# Schematics.net
KiCad netlist of a schematic drawn in Altium Designer
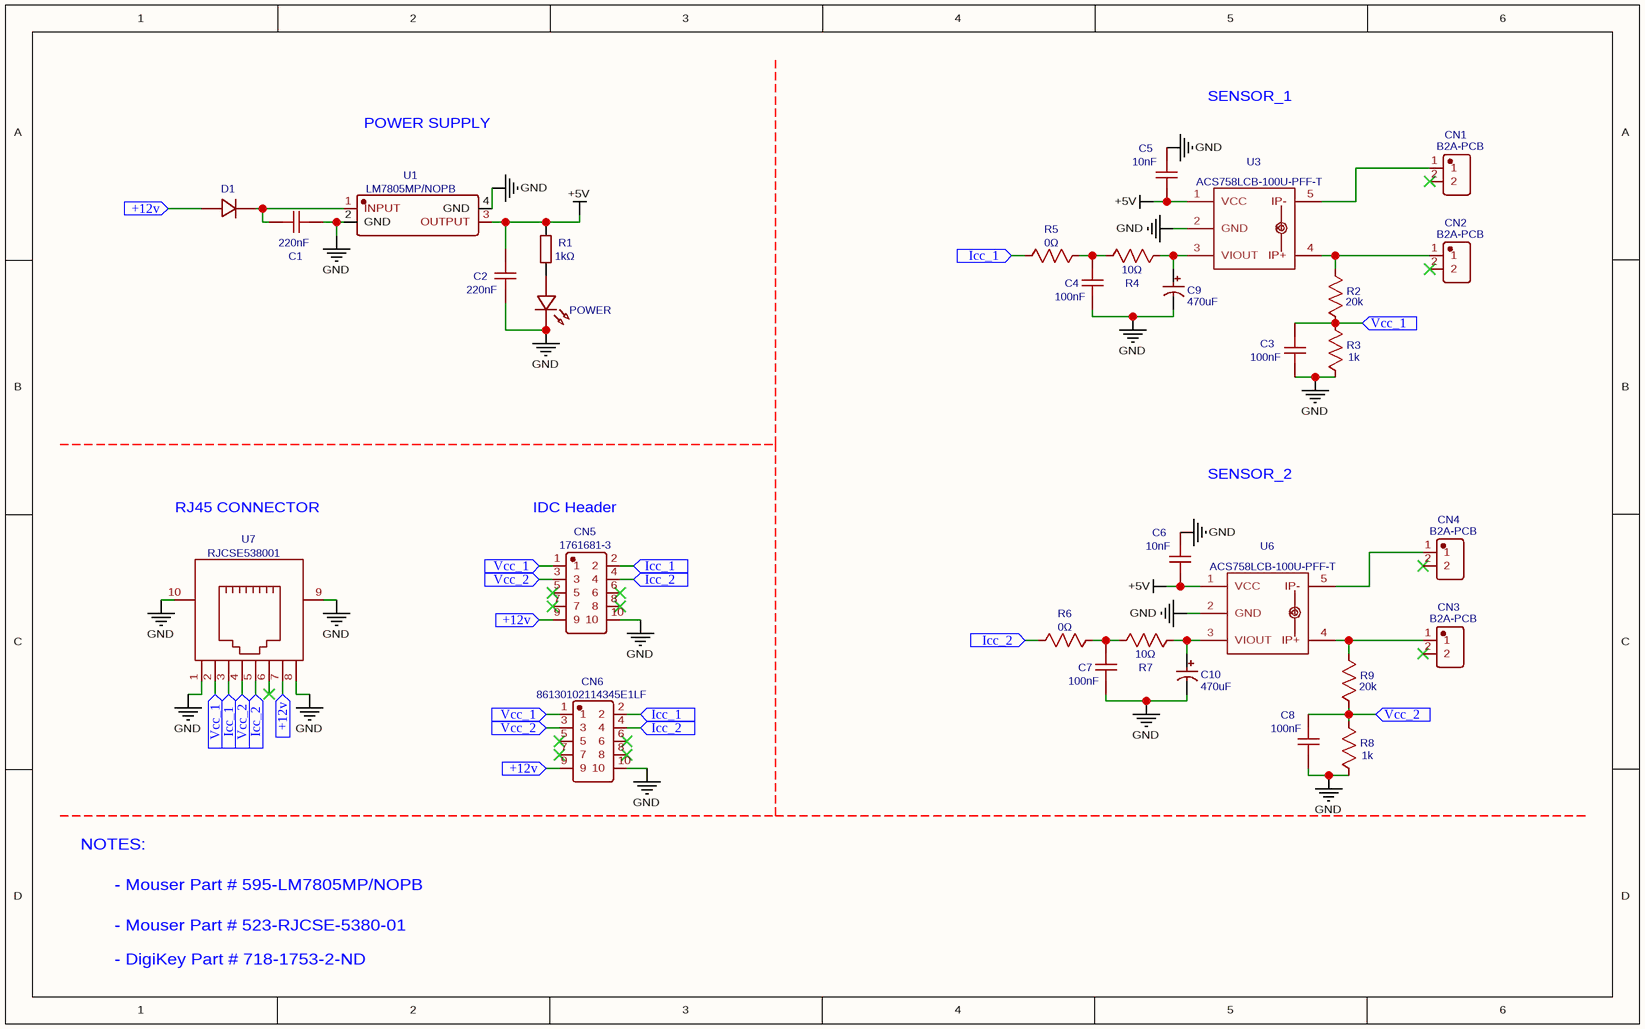
[diagram p0: Schematics.schdoc]

(export (version "E")
  (design (tool "Eeschema 10.0.6"))
  (components
    (comp (ref "C1")
      (value "220nF")
      (fields (field (name "CONTRIBUTOR") "LCEDA_Lib"))
      (libsource (lib "altium-import") (part "root_0_220nF_"))
    )
    (comp (ref "C2")
      (value "220nF")
      (fields (field (name "CONTRIBUTOR") "LCEDA_Lib"))
      (libsource (lib "altium-import") (part "root_3_220nF_"))
    )
    (comp (ref "C3")
      (value "100nF")
      (fields (field (name "CONTRIBUTOR") "LCEDA_Lib"))
      (libsource (lib "altium-import") (part "root_3_100nF_"))
    )
    (comp (ref "C4")
      (value "100nF")
      (fields (field (name "CONTRIBUTOR") "LCEDA_Lib"))
      (libsource (lib "altium-import") (part "root_3_100nF_"))
    )
    (comp (ref "C5")
      (value "10nF")
      (fields (field (name "CONTRIBUTOR") "LCEDA_Lib"))
      (libsource (lib "altium-import") (part "root_3_10nF_"))
    )
    (comp (ref "C6")
      (value "10nF")
      (fields (field (name "CONTRIBUTOR") "LCEDA_Lib"))
      (libsource (lib "altium-import") (part "root_3_10nF_"))
    )
    (comp (ref "C7")
      (value "100nF")
      (fields (field (name "CONTRIBUTOR") "LCEDA_Lib"))
      (libsource (lib "altium-import") (part "root_3_100nF_"))
    )
    (comp (ref "C8")
      (value "100nF")
      (fields (field (name "CONTRIBUTOR") "LCEDA_Lib"))
      (libsource (lib "altium-import") (part "root_3_100nF_"))
    )
    (comp (ref "C9")
      (value "470uF")
      (fields
        (field (name "MANUFACTURER") "VISHAY(威世)")
        (field (name "MANUFACTURER PART") "293D477X9010E2TE3")
        (field (name "CONTRIBUTOR") "LCSC")
      )
      (libsource (lib "altium-import") (part "root_3_470uF_"))
    )
    (comp (ref "C10")
      (value "470uF")
      (fields
        (field (name "MANUFACTURER") "VISHAY(威世)")
        (field (name "MANUFACTURER PART") "293D477X9010E2TE3")
        (field (name "CONTRIBUTOR") "LCSC")
      )
      (libsource (lib "altium-import") (part "root_3_470uF_"))
    )
    (comp (ref "CN1")
      (value "B2A-PCB")
      (fields (field (name "CONTRIBUTOR") "lcsc"))
      (libsource (lib "altium-import") (part "root_0_B2A-PCB_"))
    )
    (comp (ref "CN2")
      (value "B2A-PCB")
      (fields (field (name "CONTRIBUTOR") "lcsc"))
      (libsource (lib "altium-import") (part "root_0_B2A-PCB_"))
    )
    (comp (ref "CN3")
      (value "B2A-PCB")
      (fields (field (name "CONTRIBUTOR") "lcsc"))
      (libsource (lib "altium-import") (part "root_0_B2A-PCB_"))
    )
    (comp (ref "CN4")
      (value "B2A-PCB")
      (fields (field (name "CONTRIBUTOR") "lcsc"))
      (libsource (lib "altium-import") (part "root_0_B2A-PCB_"))
    )
    (comp (ref "CN5")
      (value "1761681-3")
      (fields (field (name "MANUFACTURER") "TE Connectivity(泰科电子)") (field (name "CONTRIBUTOR") "LCSC"))
      (libsource (lib "altium-import") (part "root_0_1761681-3_"))
    )
    (comp (ref "CN6")
      (value "86130102114345E1LF")
      (fields (field (name "MANUFACTURER") "Amphenol") (field (name "CONTRIBUTOR") "LCSC"))
      (libsource (lib "altium-import") (part "root_0_86130102114345E1LF_"))
    )
    (comp (ref "D1")
      (value "CD4148WSP-C109001")
      (fields (field (name "MANUFACTURER") "LIZ(丽智电子)") (field (name "MANUFACTURER PART") "CD4148WSP"))
      (libsource (lib "altium-import") (part "root_2_CD4148WSP-C109001_"))
    )
    (comp (ref "POWER")
      (value "LED-0805_G")
      (fields
        (field (name "MANUFACTURER") "国星光电")
        (field (name "MANUFACTURER PART") "NCD0805G1")
        (field (name "CONTRIBUTOR") "LCEDA_Lib")
      )
      (libsource (lib "altium-import") (part "root_3_LED-0805_G_"))
    )
    (comp (ref "R1")
      (value "1kΩ")
      (fields
        (field (name "MANUFACTURER") "UNI-ROYAL(厚声)")
        (field (name "MANUFACTURER PART") "0805W8F1001T5E")
      )
      (libsource (lib "altium-import") (part "root_1_1kΩ_"))
    )
    (comp (ref "R2")
      (value "20k")
      (fields (field (name "CONTRIBUTOR") "LCEDA_Lib"))
      (libsource (lib "altium-import") (part "root_1_20k_"))
    )
    (comp (ref "R3")
      (value "1k")
      (fields (field (name "CONTRIBUTOR") "LCEDA_Lib"))
      (libsource (lib "altium-import") (part "root_1_1k_"))
    )
    (comp (ref "R4")
      (value "10Ω")
      (fields (field (name "CONTRIBUTOR") "LCEDA_Lib"))
      (libsource (lib "altium-import") (part "root_2_10Ω_"))
    )
    (comp (ref "R5")
      (value "0Ω")
      (fields (field (name "CONTRIBUTOR") "LCEDA_Lib"))
      (libsource (lib "altium-import") (part "root_2_0Ω_"))
    )
    (comp (ref "R6")
      (value "0Ω")
      (fields (field (name "CONTRIBUTOR") "LCEDA_Lib"))
      (libsource (lib "altium-import") (part "root_2_0Ω_"))
    )
    (comp (ref "R7")
      (value "10Ω")
      (fields (field (name "CONTRIBUTOR") "LCEDA_Lib"))
      (libsource (lib "altium-import") (part "root_2_10Ω_"))
    )
    (comp (ref "R8")
      (value "1k")
      (fields (field (name "CONTRIBUTOR") "LCEDA_Lib"))
      (libsource (lib "altium-import") (part "root_1_1k_"))
    )
    (comp (ref "R9")
      (value "20k")
      (fields (field (name "CONTRIBUTOR") "LCEDA_Lib"))
      (libsource (lib "altium-import") (part "root_1_20k_"))
    )
    (comp (ref "U1")
      (value "LM7805MP/NOPB")
      (fields (field (name "MANUFACTURER") "TI(德州仪器)") (field (name "CONTRIBUTOR") "LCSC"))
      (libsource (lib "altium-import") (part "root_0_LM7805MP/NOPB_"))
    )
    (comp (ref "U3")
      (value "ACS758LCB-100U-PFF-T")
      (fields
        (field (name "MANUFACTURER") "ALLEGRO(美国埃戈罗)")
        (field (name "MANUFACTURER PART") "ACS758LCB-100B-PFF-T")
      )
      (libsource (lib "altium-import") (part "root_2_ACS758LCB-100U-PFF-T_"))
    )
    (comp (ref "U6")
      (value "ACS758LCB-100U-PFF-T")
      (fields
        (field (name "MANUFACTURER") "ALLEGRO(美国埃戈罗)")
        (field (name "MANUFACTURER PART") "ACS758LCB-100B-PFF-T")
      )
      (libsource (lib "altium-import") (part "root_2_ACS758LCB-100U-PFF-T_"))
    )
    (comp (ref "U7")
      (value "RJCSE538001")
      (fields (field (name "MANUFACTURER") "Amphenol") (field (name "CONTRIBUTOR") "lcsc"))
      (libsource (lib "altium-import") (part "root_0_RJCSE538001_"))
    )
  )
  (nets
    (net (code "1") (name "+5V") (class "Default")
      (node (ref "C2") (pin "1") (pinfunction "1_1") (pintype "passive"))
      (node (ref "C5") (pin "2") (pinfunction "2_2") (pintype "passive"))
      (node (ref "C6") (pin "2") (pinfunction "2_2") (pintype "passive"))
      (node (ref "R1") (pin "2") (pinfunction "2_2") (pintype "passive"))
      (node (ref "U1") (pin "3") (pinfunction "OUTPUT_3") (pintype "passive"))
      (node (ref "U3") (pin "1") (pinfunction "VCC_1") (pintype "passive"))
      (node (ref "U6") (pin "1") (pinfunction "VCC_1") (pintype "passive"))
    )
    (net (code "2") (name "/+12v") (class "Default")
      (node (ref "CN5") (pin "9") (pinfunction "9_9") (pintype "passive"))
      (node (ref "CN6") (pin "9") (pinfunction "9_9") (pintype "passive"))
      (node (ref "D1") (pin "2") (pinfunction "2_2") (pintype "passive"))
      (node (ref "U7") (pin "7") (pinfunction "7_7") (pintype "passive"))
    )
    (net (code "3") (name "/Icc_1") (class "Default")
      (node (ref "CN5") (pin "2") (pinfunction "2_2") (pintype "passive"))
      (node (ref "CN6") (pin "2") (pinfunction "2_2") (pintype "passive"))
      (node (ref "R5") (pin "2") (pinfunction "2_2") (pintype "passive"))
      (node (ref "U7") (pin "3") (pinfunction "3_3") (pintype "passive"))
    )
    (net (code "4") (name "/Icc_2") (class "Default")
      (node (ref "CN5") (pin "4") (pinfunction "4_4") (pintype "passive"))
      (node (ref "CN6") (pin "4") (pinfunction "4_4") (pintype "passive"))
      (node (ref "R6") (pin "2") (pinfunction "2_2") (pintype "passive"))
      (node (ref "U7") (pin "5") (pinfunction "5_5") (pintype "passive"))
    )
    (net (code "5") (name "/Vcc_1") (class "Default")
      (node (ref "C3") (pin "1") (pinfunction "1_1") (pintype "passive"))
      (node (ref "CN5") (pin "1") (pinfunction "1_1") (pintype "passive"))
      (node (ref "CN6") (pin "1") (pinfunction "1_1") (pintype "passive"))
      (node (ref "R2") (pin "1") (pinfunction "1_1") (pintype "passive"))
      (node (ref "R3") (pin "2") (pinfunction "2_2") (pintype "passive"))
      (node (ref "U7") (pin "2") (pinfunction "2_2") (pintype "passive"))
    )
    (net (code "6") (name "/Vcc_2") (class "Default")
      (node (ref "C8") (pin "1") (pinfunction "1_1") (pintype "passive"))
      (node (ref "CN5") (pin "3") (pinfunction "3_3") (pintype "passive"))
      (node (ref "CN6") (pin "3") (pinfunction "3_3") (pintype "passive"))
      (node (ref "R8") (pin "2") (pinfunction "2_2") (pintype "passive"))
      (node (ref "R9") (pin "1") (pinfunction "1_1") (pintype "passive"))
      (node (ref "U7") (pin "4") (pinfunction "4_4") (pintype "passive"))
    )
    (net (code "7") (name "GND") (class "Default")
      (node (ref "C1") (pin "2") (pinfunction "2_2") (pintype "passive"))
      (node (ref "C10") (pin "2") (pinfunction "2_2") (pintype "passive"))
      (node (ref "C2") (pin "2") (pinfunction "2_2") (pintype "passive"))
      (node (ref "C3") (pin "2") (pinfunction "2_2") (pintype "passive"))
      (node (ref "C4") (pin "2") (pinfunction "2_2") (pintype "passive"))
      (node (ref "C5") (pin "1") (pinfunction "1_1") (pintype "passive"))
      (node (ref "C6") (pin "1") (pinfunction "1_1") (pintype "passive"))
      (node (ref "C7") (pin "2") (pinfunction "2_2") (pintype "passive"))
      (node (ref "C8") (pin "2") (pinfunction "2_2") (pintype "passive"))
      (node (ref "C9") (pin "2") (pinfunction "2_2") (pintype "passive"))
      (node (ref "CN5") (pin "10") (pinfunction "10_10") (pintype "passive"))
      (node (ref "CN6") (pin "10") (pinfunction "10_10") (pintype "passive"))
      (node (ref "POWER") (pin "2") (pinfunction "2_2") (pintype "passive"))
      (node (ref "R3") (pin "1") (pinfunction "1_1") (pintype "passive"))
      (node (ref "R8") (pin "1") (pinfunction "1_1") (pintype "passive"))
      (node (ref "U1") (pin "2") (pinfunction "GND_2") (pintype "passive"))
      (node (ref "U1") (pin "4") (pinfunction "GND_4") (pintype "passive"))
      (node (ref "U3") (pin "2") (pinfunction "GND_2") (pintype "passive"))
      (node (ref "U6") (pin "2") (pinfunction "GND_2") (pintype "passive"))
      (node (ref "U7") (pin "1") (pinfunction "1_1") (pintype "passive"))
      (node (ref "U7") (pin "10") (pinfunction "EH_10") (pintype "passive"))
      (node (ref "U7") (pin "8") (pinfunction "8_8") (pintype "passive"))
      (node (ref "U7") (pin "9") (pinfunction "EH_9") (pintype "passive"))
    )
    (net (code "8") (name "Net-(C4-Pad1)") (class "Default")
      (node (ref "C4") (pin "1") (pinfunction "1_1") (pintype "passive"))
      (node (ref "R4") (pin "2") (pinfunction "2_2") (pintype "passive"))
      (node (ref "R5") (pin "1") (pinfunction "1_1") (pintype "passive"))
    )
    (net (code "9") (name "Net-(C7-Pad1)") (class "Default")
      (node (ref "C7") (pin "1") (pinfunction "1_1") (pintype "passive"))
      (node (ref "R6") (pin "1") (pinfunction "1_1") (pintype "passive"))
      (node (ref "R7") (pin "2") (pinfunction "2_2") (pintype "passive"))
    )
    (net (code "10") (name "Net-(POWER-Pad1)") (class "Default")
      (node (ref "POWER") (pin "1") (pinfunction "1_1") (pintype "passive"))
      (node (ref "R1") (pin "1") (pinfunction "1_1") (pintype "passive"))
    )
    (net (code "11") (name "Net-(U1-INPUT)") (class "Default")
      (node (ref "C1") (pin "1") (pinfunction "1_1") (pintype "passive"))
      (node (ref "D1") (pin "1") (pinfunction "1_1") (pintype "passive"))
      (node (ref "U1") (pin "1") (pinfunction "INPUT_1") (pintype "passive"))
    )
    (net (code "12") (name "Net-(U3-IP+)") (class "Default")
      (node (ref "CN2") (pin "1") (pinfunction "1_1") (pintype "passive"))
      (node (ref "R2") (pin "2") (pinfunction "2_2") (pintype "passive"))
      (node (ref "U3") (pin "4") (pinfunction "IP+_4") (pintype "passive"))
    )
    (net (code "13") (name "Net-(U3-IP-)") (class "Default")
      (node (ref "CN1") (pin "1") (pinfunction "1_1") (pintype "passive"))
      (node (ref "U3") (pin "5") (pinfunction "IP-_5") (pintype "passive"))
    )
    (net (code "14") (name "Net-(U3-VIOUT)") (class "Default")
      (node (ref "C9") (pin "1") (pinfunction "1_1") (pintype "passive"))
      (node (ref "R4") (pin "1") (pinfunction "1_1") (pintype "passive"))
      (node (ref "U3") (pin "3") (pinfunction "VIOUT_3") (pintype "passive"))
    )
    (net (code "15") (name "Net-(U6-IP+)") (class "Default")
      (node (ref "CN3") (pin "1") (pinfunction "1_1") (pintype "passive"))
      (node (ref "R9") (pin "2") (pinfunction "2_2") (pintype "passive"))
      (node (ref "U6") (pin "4") (pinfunction "IP+_4") (pintype "passive"))
    )
    (net (code "16") (name "Net-(U6-IP-)") (class "Default")
      (node (ref "CN4") (pin "1") (pinfunction "1_1") (pintype "passive"))
      (node (ref "U6") (pin "5") (pinfunction "IP-_5") (pintype "passive"))
    )
    (net (code "17") (name "Net-(U6-VIOUT)") (class "Default")
      (node (ref "C10") (pin "1") (pinfunction "1_1") (pintype "passive"))
      (node (ref "R7") (pin "1") (pinfunction "1_1") (pintype "passive"))
      (node (ref "U6") (pin "3") (pinfunction "VIOUT_3") (pintype "passive"))
    )
    (net (code "18") (name "unconnected-(CN1-Pad2)") (class "Default")
      (node (ref "CN1") (pin "2") (pinfunction "2_2") (pintype "passive+no_connect"))
    )
    (net (code "19") (name "unconnected-(CN2-Pad2)") (class "Default")
      (node (ref "CN2") (pin "2") (pinfunction "2_2") (pintype "passive+no_connect"))
    )
    (net (code "20") (name "unconnected-(CN3-Pad2)") (class "Default")
      (node (ref "CN3") (pin "2") (pinfunction "2_2") (pintype "passive+no_connect"))
    )
    (net (code "21") (name "unconnected-(CN4-Pad2)") (class "Default")
      (node (ref "CN4") (pin "2") (pinfunction "2_2") (pintype "passive+no_connect"))
    )
    (net (code "22") (name "unconnected-(CN5-Pad5)") (class "Default")
      (node (ref "CN5") (pin "5") (pinfunction "5_5") (pintype "passive+no_connect"))
    )
    (net (code "23") (name "unconnected-(CN5-Pad6)") (class "Default")
      (node (ref "CN5") (pin "6") (pinfunction "6_6") (pintype "passive+no_connect"))
    )
    (net (code "24") (name "unconnected-(CN5-Pad7)") (class "Default")
      (node (ref "CN5") (pin "7") (pinfunction "7_7") (pintype "passive+no_connect"))
    )
    (net (code "25") (name "unconnected-(CN5-Pad8)") (class "Default")
      (node (ref "CN5") (pin "8") (pinfunction "8_8") (pintype "passive+no_connect"))
    )
    (net (code "26") (name "unconnected-(CN6-Pad5)") (class "Default")
      (node (ref "CN6") (pin "5") (pinfunction "5_5") (pintype "passive+no_connect"))
    )
    (net (code "27") (name "unconnected-(CN6-Pad6)") (class "Default")
      (node (ref "CN6") (pin "6") (pinfunction "6_6") (pintype "passive+no_connect"))
    )
    (net (code "28") (name "unconnected-(CN6-Pad7)") (class "Default")
      (node (ref "CN6") (pin "7") (pinfunction "7_7") (pintype "passive+no_connect"))
    )
    (net (code "29") (name "unconnected-(CN6-Pad8)") (class "Default")
      (node (ref "CN6") (pin "8") (pinfunction "8_8") (pintype "passive+no_connect"))
    )
    (net (code "30") (name "unconnected-(U7-Pad6)") (class "Default")
      (node (ref "U7") (pin "6") (pinfunction "6_6") (pintype "passive+no_connect"))
    )
  )
)
